# semaforo.net
KiCad netlist of a schematic drawn in EAGLE
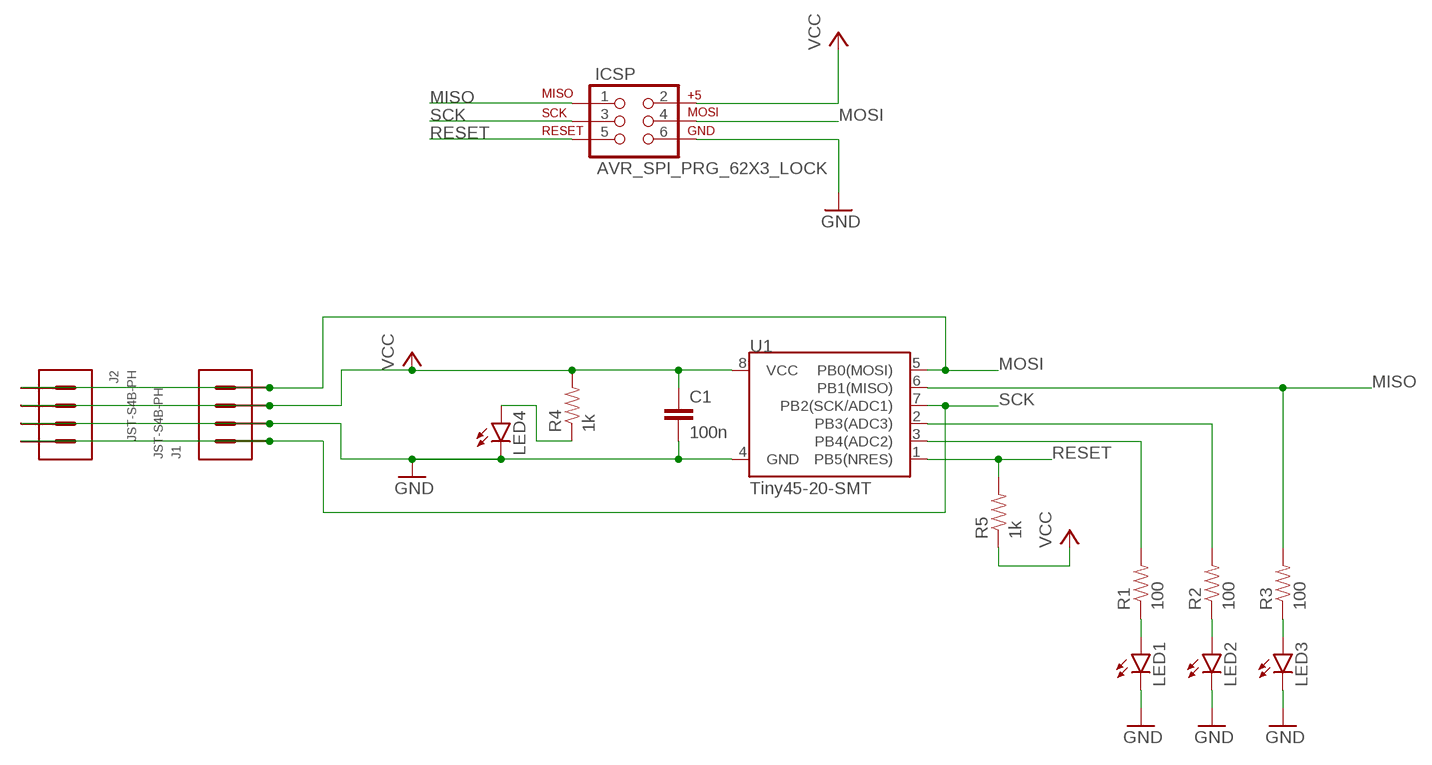
[diagram p0: schematic, sheet 1]

(export (version "E")
  (design (tool "Eeschema 10.0.6"))
  (components
    (comp (ref "C1")
      (value "100n")
      (footprint "eagle-import:1206")
      (libsource (lib "eagle-import") (part "CAP1206"))
    )
    (comp (ref "ICSP")
      (value "AVR_SPI_PRG_62X3_LOCK")
      (footprint "eagle-import:2X3_LOCK")
      (libsource (lib "eagle-import") (part "AVR_SPI_PRG_62X3_LOCK"))
    )
    (comp (ref "J1")
      (value "JST-S4B-PH")
      (footprint "eagle-import:JST-S4B-PH")
      (libsource (lib "eagle-import") (part "JST-S4B-PH"))
    )
    (comp (ref "J2")
      (value "JST-S4B-PH")
      (footprint "eagle-import:JST-S4B-PH")
      (libsource (lib "eagle-import") (part "JST-S4B-PH"))
    )
    (comp (ref "LED1")
      (value "LED5MM")
      (footprint "eagle-import:LED5MM")
      (libsource (lib "eagle-import") (part "LED5MM"))
    )
    (comp (ref "LED2")
      (value "LED5MM")
      (footprint "eagle-import:LED5MM")
      (libsource (lib "eagle-import") (part "LED5MM"))
    )
    (comp (ref "LED3")
      (value "LED5MM")
      (footprint "eagle-import:LED5MM")
      (libsource (lib "eagle-import") (part "LED5MM"))
    )
    (comp (ref "LED4")
      (value "LED1206")
      (footprint "eagle-import:LED-1206")
      (libsource (lib "eagle-import") (part "LED1206"))
    )
    (comp (ref "R1")
      (value "100")
      (footprint "eagle-import:1206")
      (libsource (lib "eagle-import") (part "RESISTOR1206"))
    )
    (comp (ref "R2")
      (value "100")
      (footprint "eagle-import:1206")
      (libsource (lib "eagle-import") (part "RESISTOR1206"))
    )
    (comp (ref "R3")
      (value "100")
      (footprint "eagle-import:1206")
      (libsource (lib "eagle-import") (part "RESISTOR1206"))
    )
    (comp (ref "R4")
      (value "1k")
      (footprint "eagle-import:1206")
      (libsource (lib "eagle-import") (part "RESISTOR1206"))
    )
    (comp (ref "R5")
      (value "1k")
      (footprint "eagle-import:1206")
      (libsource (lib "eagle-import") (part "RESISTOR1206"))
    )
    (comp (ref "U1")
      (value "Tiny45-20-SMT")
      (footprint "eagle-import:SO08-EIAJ")
      (libsource (lib "eagle-import") (part "ATTINY45TINY45-20-SMT"))
    )
  )
  (nets
    (net (code "1") (name "/MISO") (class "Default")
      (node (ref "ICSP") (pin "1") (pinfunction "1_1") (pintype "passive"))
      (node (ref "R3") (pin "2") (pinfunction "2_2") (pintype "passive"))
      (node (ref "U1") (pin "6") (pinfunction "PB1(MISO)_6") (pintype "bidirectional"))
    )
    (net (code "2") (name "/MOSI") (class "Default")
      (node (ref "ICSP") (pin "4") (pinfunction "4_4") (pintype "passive"))
      (node (ref "J1") (pin "P$4") (pinfunction "P$4_P$4") (pintype "bidirectional"))
      (node (ref "J2") (pin "P$1") (pinfunction "P$1_P$1") (pintype "bidirectional"))
      (node (ref "U1") (pin "5") (pinfunction "PB0(MOSI)_5") (pintype "bidirectional"))
    )
    (net (code "3") (name "/RESET") (class "Default")
      (node (ref "ICSP") (pin "5") (pinfunction "5_5") (pintype "passive"))
      (node (ref "R5") (pin "2") (pinfunction "2_2") (pintype "passive"))
      (node (ref "U1") (pin "1") (pinfunction "PB5(NRES)_1") (pintype "bidirectional"))
    )
    (net (code "4") (name "/SCK") (class "Default")
      (node (ref "ICSP") (pin "3") (pinfunction "3_3") (pintype "passive"))
      (node (ref "J1") (pin "P$1") (pinfunction "P$1_P$1") (pintype "bidirectional"))
      (node (ref "J2") (pin "P$4") (pinfunction "P$4_P$4") (pintype "bidirectional"))
      (node (ref "U1") (pin "7") (pinfunction "PB2(SCK/ADC1)_7") (pintype "bidirectional"))
    )
    (net (code "5") (name "GND") (class "Default")
      (node (ref "C1") (pin "2") (pinfunction "2_2") (pintype "passive"))
      (node (ref "ICSP") (pin "6") (pinfunction "6_6") (pintype "passive"))
      (node (ref "J1") (pin "P$2") (pinfunction "P$2_P$2") (pintype "bidirectional"))
      (node (ref "J2") (pin "P$3") (pinfunction "P$3_P$3") (pintype "bidirectional"))
      (node (ref "LED1") (pin "K") (pinfunction "C_K") (pintype "passive"))
      (node (ref "LED2") (pin "K") (pinfunction "C_K") (pintype "passive"))
      (node (ref "LED3") (pin "K") (pinfunction "C_K") (pintype "passive"))
      (node (ref "LED4") (pin "C") (pinfunction "C_C") (pintype "passive"))
      (node (ref "U1") (pin "4") (pinfunction "GND_4") (pintype "bidirectional"))
    )
    (net (code "6") (name "Net-(LED1-PadA)") (class "Default")
      (node (ref "LED1") (pin "A") (pinfunction "A_A") (pintype "passive"))
      (node (ref "R1") (pin "1") (pinfunction "1_1") (pintype "passive"))
    )
    (net (code "7") (name "Net-(LED2-PadA)") (class "Default")
      (node (ref "LED2") (pin "A") (pinfunction "A_A") (pintype "passive"))
      (node (ref "R2") (pin "1") (pinfunction "1_1") (pintype "passive"))
    )
    (net (code "8") (name "Net-(LED3-PadA)") (class "Default")
      (node (ref "LED3") (pin "A") (pinfunction "A_A") (pintype "passive"))
      (node (ref "R3") (pin "1") (pinfunction "1_1") (pintype "passive"))
    )
    (net (code "9") (name "Net-(LED4-PadA)") (class "Default")
      (node (ref "LED4") (pin "A") (pinfunction "A_A") (pintype "passive"))
      (node (ref "R4") (pin "1") (pinfunction "1_1") (pintype "passive"))
    )
    (net (code "10") (name "Net-(U1-PB3(ADC3))") (class "Default")
      (node (ref "R2") (pin "2") (pinfunction "2_2") (pintype "passive"))
      (node (ref "U1") (pin "2") (pinfunction "PB3(ADC3)_2") (pintype "bidirectional"))
    )
    (net (code "11") (name "Net-(U1-PB4(ADC2))") (class "Default")
      (node (ref "R1") (pin "2") (pinfunction "2_2") (pintype "passive"))
      (node (ref "U1") (pin "3") (pinfunction "PB4(ADC2)_3") (pintype "bidirectional"))
    )
    (net (code "12") (name "VCC") (class "Default")
      (node (ref "C1") (pin "1") (pinfunction "1_1") (pintype "passive"))
      (node (ref "ICSP") (pin "2") (pinfunction "2_2") (pintype "passive"))
      (node (ref "J1") (pin "P$3") (pinfunction "P$3_P$3") (pintype "bidirectional"))
      (node (ref "J2") (pin "P$2") (pinfunction "P$2_P$2") (pintype "bidirectional"))
      (node (ref "R4") (pin "2") (pinfunction "2_2") (pintype "passive"))
      (node (ref "R5") (pin "1") (pinfunction "1_1") (pintype "passive"))
      (node (ref "U1") (pin "8") (pinfunction "VCC_8") (pintype "bidirectional"))
    )
  )
)
